# Laptimer.net
KiCad netlist of a schematic drawn in EAGLE
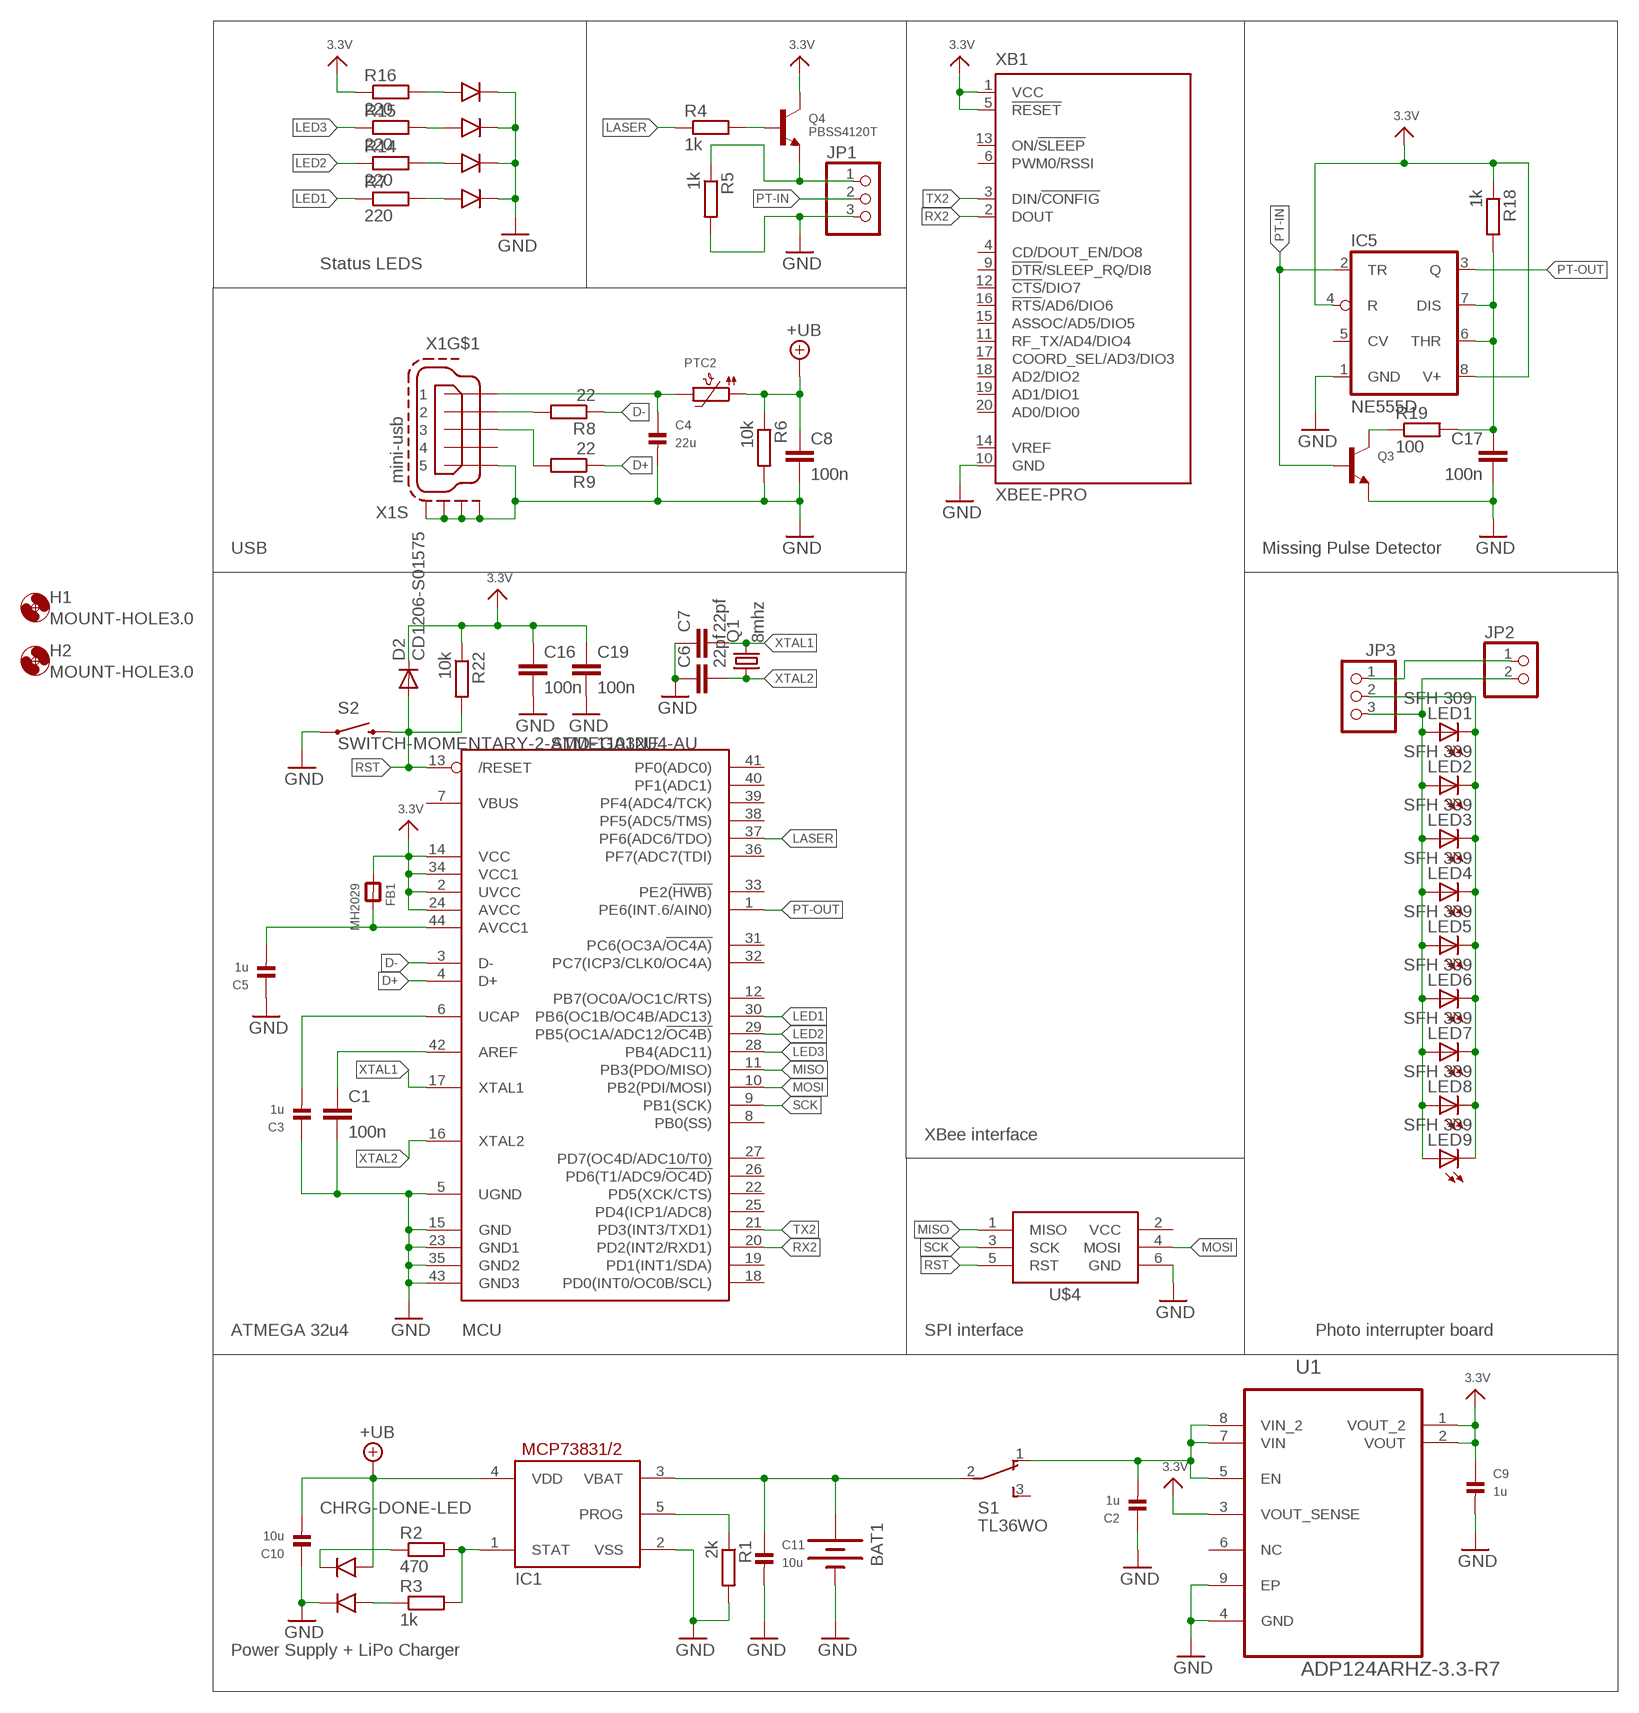
[diagram p0: schematic, sheet 1]

(export (version "E")
  (design (tool "Eeschema 10.0.6"))
  (components
    (comp (ref "BAT1")
      (value "BATTERY18650")
      (footprint "eagle-import:BATTERY_18650-HOLDER")
      (libsource (lib "eagle-import") (part "BATTERY18650"))
    )
    (comp (ref "C1")
      (value "100n")
      (footprint "eagle-import:C0603K")
      (libsource (lib "eagle-import") (part "C-EUC0603K"))
    )
    (comp (ref "C2")
      (value "1u")
      (footprint "eagle-import:_0805MP")
      (libsource (lib "eagle-import") (part "CAP_CERAMIC_0805MP"))
    )
    (comp (ref "C3")
      (value "1u")
      (footprint "eagle-import:_0805MP")
      (libsource (lib "eagle-import") (part "CAP_CERAMIC_0805MP"))
    )
    (comp (ref "C4")
      (value "22u")
      (footprint "eagle-import:_0805MP")
      (libsource (lib "eagle-import") (part "CAP_CERAMIC_0805MP"))
    )
    (comp (ref "C5")
      (value "1u")
      (footprint "eagle-import:_0805MP")
      (libsource (lib "eagle-import") (part "CAP_CERAMIC_0805MP"))
    )
    (comp (ref "C6")
      (value "22pf")
      (footprint "eagle-import:C0603K")
      (libsource (lib "eagle-import") (part "C-EUC0603K"))
    )
    (comp (ref "C7")
      (value "22pf")
      (footprint "eagle-import:C0603K")
      (libsource (lib "eagle-import") (part "C-EUC0603K"))
    )
    (comp (ref "C8")
      (value "100n")
      (footprint "eagle-import:C0603K")
      (libsource (lib "eagle-import") (part "C-EUC0603K"))
    )
    (comp (ref "C9")
      (value "1u")
      (footprint "eagle-import:_0805MP")
      (libsource (lib "eagle-import") (part "CAP_CERAMIC_0805MP"))
    )
    (comp (ref "C10")
      (value "10u")
      (footprint "eagle-import:_0805MP")
      (libsource (lib "eagle-import") (part "CAP_CERAMIC_0805MP"))
    )
    (comp (ref "C11")
      (value "10u")
      (footprint "eagle-import:_0805MP")
      (libsource (lib "eagle-import") (part "CAP_CERAMIC_0805MP"))
    )
    (comp (ref "C16")
      (value "100n")
      (footprint "eagle-import:C0603K")
      (libsource (lib "eagle-import") (part "C-EUC0603K"))
    )
    (comp (ref "C17")
      (value "100n")
      (footprint "eagle-import:C0603K")
      (libsource (lib "eagle-import") (part "C-EUC0603K"))
    )
    (comp (ref "C19")
      (value "100n")
      (footprint "eagle-import:C0603K")
      (libsource (lib "eagle-import") (part "C-EUC0603K"))
    )
    (comp (ref "D2")
      (value "CD1206-S01575")
      (footprint "eagle-import:MINIMELF")
      (libsource (lib "eagle-import") (part "DIODE-MINIMELF"))
    )
    (comp (ref "FB1")
      (value "MH2029")
      (footprint "eagle-import:_0805MP")
      (libsource (lib "eagle-import") (part "FERRITE_0805MP"))
    )
    (comp (ref "H1")
      (value "MOUNT-HOLE3.0")
      (footprint "eagle-import:3,0")
      (libsource (lib "eagle-import") (part "MOUNT-HOLE3.0"))
    )
    (comp (ref "H2")
      (value "MOUNT-HOLE3.0")
      (footprint "eagle-import:3,0")
      (libsource (lib "eagle-import") (part "MOUNT-HOLE3.0"))
    )
    (comp (ref "IC1")
      (value "MCP73831/OT")
      (footprint "eagle-import:SOT23-5L")
      (libsource (lib "eagle-import") (part "MCP73831/OT"))
    )
    (comp (ref "IC5")
      (value "NE555D")
      (footprint "eagle-import:SO08")
      (libsource (lib "eagle-import") (part "555DNE"))
    )
    (comp (ref "JP1")
      (value "PINHD-1X3")
      (footprint "eagle-import:1X03")
      (libsource (lib "eagle-import") (part "PINHD-1X3"))
    )
    (comp (ref "JP2")
      (value "HEADER-1X2ROUND")
      (footprint "eagle-import:1X02_ROUND")
      (libsource (lib "eagle-import") (part "HEADER-1X2ROUND"))
    )
    (comp (ref "JP3")
      (value "PINHD-1X3")
      (footprint "eagle-import:1X03")
      (libsource (lib "eagle-import") (part "PINHD-1X3"))
    )
    (comp (ref "LED1")
      (value "SFH 309")
      (footprint "eagle-import:LED3MM")
      (libsource (lib "eagle-import") (part "LED3MM"))
    )
    (comp (ref "LED2")
      (value "SFH 309")
      (footprint "eagle-import:LED3MM")
      (libsource (lib "eagle-import") (part "LED3MM"))
    )
    (comp (ref "LED3")
      (value "SFH 309")
      (footprint "eagle-import:LED3MM")
      (libsource (lib "eagle-import") (part "LED3MM"))
    )
    (comp (ref "LED4")
      (value "SFH 309")
      (footprint "eagle-import:LED3MM")
      (libsource (lib "eagle-import") (part "LED3MM"))
    )
    (comp (ref "LED5")
      (value "SFH 309")
      (footprint "eagle-import:LED3MM")
      (libsource (lib "eagle-import") (part "LED3MM"))
    )
    (comp (ref "LED6")
      (value "SFH 309")
      (footprint "eagle-import:LED3MM")
      (libsource (lib "eagle-import") (part "LED3MM"))
    )
    (comp (ref "LED7")
      (value "SFH 309")
      (footprint "eagle-import:LED3MM")
      (libsource (lib "eagle-import") (part "LED3MM"))
    )
    (comp (ref "LED8")
      (value "SFH 309")
      (footprint "eagle-import:LED3MM")
      (libsource (lib "eagle-import") (part "LED3MM"))
    )
    (comp (ref "LED9")
      (value "SFH 309")
      (footprint "eagle-import:LED3MM")
      (libsource (lib "eagle-import") (part "LED3MM"))
    )
    (comp (ref "MCU")
      (value "ATMEGA32U4-AU")
      (footprint "eagle-import:TQFP44")
      (libsource (lib "eagle-import") (part "ATMEGA32U4-AU"))
    )
    (comp (ref "PTC2")
      (value "PTC1206")
      (footprint "eagle-import:1206")
      (libsource (lib "eagle-import") (part "PTC1206"))
    )
    (comp (ref "Q1")
      (value "8mhz")
      (footprint "eagle-import:HC49_S")
      (libsource (lib "eagle-import") (part "CRYSTALHC49S"))
    )
    (comp (ref "Q3")
      (value "TRANSISTOR_NPNWIDE")
      (footprint "eagle-import:SOT23-WIDE")
      (libsource (lib "eagle-import") (part "TRANSISTOR_NPNWIDE"))
    )
    (comp (ref "Q4")
      (value "PBSS4120T")
      (footprint "eagle-import:SOT23-WIDE")
      (libsource (lib "eagle-import") (part "TRANSISTOR_NPNWIDE"))
    )
    (comp (ref "R1")
      (value "2k")
      (footprint "eagle-import:R0603")
      (libsource (lib "eagle-import") (part "R-EU_R0603"))
    )
    (comp (ref "R2")
      (value "470")
      (footprint "eagle-import:R0603")
      (libsource (lib "eagle-import") (part "R-EU_R0603"))
    )
    (comp (ref "R3")
      (value "1k")
      (footprint "eagle-import:R0603")
      (libsource (lib "eagle-import") (part "R-EU_R0603"))
    )
    (comp (ref "R4")
      (value "1k")
      (footprint "eagle-import:R0603")
      (libsource (lib "eagle-import") (part "R-EU_R0603"))
    )
    (comp (ref "R5")
      (value "1k")
      (footprint "eagle-import:R0603")
      (libsource (lib "eagle-import") (part "R-EU_R0603"))
    )
    (comp (ref "R6")
      (value "10k")
      (footprint "eagle-import:R0603")
      (libsource (lib "eagle-import") (part "R-EU_R0603"))
    )
    (comp (ref "R7")
      (value "220")
      (footprint "eagle-import:R0603")
      (libsource (lib "eagle-import") (part "R-EU_R0603"))
    )
    (comp (ref "R8")
      (value "22")
      (footprint "eagle-import:R0603")
      (libsource (lib "eagle-import") (part "R-EU_R0603"))
    )
    (comp (ref "R9")
      (value "22")
      (footprint "eagle-import:R0603")
      (libsource (lib "eagle-import") (part "R-EU_R0603"))
    )
    (comp (ref "R14")
      (value "220")
      (footprint "eagle-import:R0603")
      (libsource (lib "eagle-import") (part "R-EU_R0603"))
    )
    (comp (ref "R15")
      (value "220")
      (footprint "eagle-import:R0603")
      (libsource (lib "eagle-import") (part "R-EU_R0603"))
    )
    (comp (ref "R16")
      (value "220")
      (footprint "eagle-import:R0603")
      (libsource (lib "eagle-import") (part "R-EU_R0603"))
    )
    (comp (ref "R18")
      (value "1k")
      (footprint "eagle-import:R0603")
      (libsource (lib "eagle-import") (part "R-EU_R0603"))
    )
    (comp (ref "R19")
      (value "100")
      (footprint "eagle-import:R0603")
      (libsource (lib "eagle-import") (part "R-EU_R0603"))
    )
    (comp (ref "R22")
      (value "10k")
      (footprint "eagle-import:R0603")
      (libsource (lib "eagle-import") (part "R-EU_R0603"))
    )
    (comp (ref "S1")
      (value "TL36WO")
      (footprint "eagle-import:TL3XWO")
      (libsource (lib "eagle-import") (part "TL36WO"))
    )
    (comp (ref "S2")
      (value "SWITCH-MOMENTARY-2-SMD-1101NE")
      (footprint "eagle-import:TACTILE-SWITCH-1101NE")
      (libsource (lib "eagle-import") (part "SWITCH-MOMENTARY-2-SMD-1101NE"))
    )
    (comp (ref "U$1")
      (value "BI-LEVEL-LED-INDICATOR")
      (footprint "eagle-import:BI-LEVEL-LED-INDICATOR")
      (libsource (lib "eagle-import") (part "BI-LEVEL-LED-INDICATOR"))
    )
    (comp (ref "U$4")
      (value "AVRISP-BOX")
      (footprint "eagle-import:AVRISP-BOX")
      (libsource (lib "eagle-import") (part "AVRISP-BOX"))
    )
    (comp (ref "U$18")
      (value "BI-LEVEL-LED-INDICATOR")
      (footprint "eagle-import:BI-LEVEL-LED-INDICATOR")
      (libsource (lib "eagle-import") (part "BI-LEVEL-LED-INDICATOR"))
    )
    (comp (ref "U$19")
      (value "BI-LEVEL-LED-INDICATOR")
      (footprint "eagle-import:BI-LEVEL-LED-INDICATOR")
      (libsource (lib "eagle-import") (part "BI-LEVEL-LED-INDICATOR"))
    )
    (comp (ref "U1")
      (value "ADP124ARHZ-3.3-R7")
      (footprint "eagle-import:SOP65P490X110-9N")
      (libsource (lib "eagle-import") (part "ADP124ARHZ-3.3-R7"))
    )
    (comp (ref "X1")
      (value "mini-usb")
      (footprint "eagle-import:32005-301")
      (libsource (lib "eagle-import") (part "MINI-USB-SCHIELD-32005-301"))
    )
    (comp (ref "XB1")
      (value "XBEE-PRO")
      (footprint "eagle-import:XBEE-PRO")
      (libsource (lib "eagle-import") (part "XBEE-PRO"))
    )
  )
  (nets
    (net (code "1") (name "+UB") (class "Default")
      (node (ref "C10") (pin "2") (pinfunction "P$2_2") (pintype "passive"))
      (node (ref "C8") (pin "1") (pinfunction "1_1") (pintype "passive"))
      (node (ref "IC1") (pin "4") (pinfunction "VDD_4") (pintype "power_in"))
      (node (ref "PTC2") (pin "1") (pinfunction "1_1") (pintype "passive"))
      (node (ref "R6") (pin "1") (pinfunction "1_1") (pintype "passive"))
      (node (ref "U$1") (pin "ANODE1") (pinfunction "ANODE1_ANODE1") (pintype "bidirectional"))
    )
    (net (code "2") (name "/CHRG-DONE-LED") (class "Default")
      (node (ref "R3") (pin "1") (pinfunction "1_1") (pintype "passive"))
      (node (ref "U$1") (pin "ANODE2") (pinfunction "ANODE2_ANODE2") (pintype "bidirectional"))
    )
    (net (code "3") (name "/VCC") (class "Default")
      (node (ref "U$4") (pin "2") (pinfunction "VCC_2") (pintype "power_in"))
    )
    (net (code "4") (name "3.3V") (class "Default")
      (node (ref "C16") (pin "1") (pinfunction "1_1") (pintype "passive"))
      (node (ref "C19") (pin "1") (pinfunction "1_1") (pintype "passive"))
      (node (ref "C9") (pin "1") (pinfunction "P$1_1") (pintype "passive"))
      (node (ref "D2") (pin "C") (pinfunction "C_C") (pintype "passive"))
      (node (ref "FB1") (pin "1") (pinfunction "P$1_1") (pintype "passive"))
      (node (ref "IC5") (pin "4") (pinfunction "R_4") (pintype "input"))
      (node (ref "IC5") (pin "8") (pinfunction "V+_8") (pintype "power_in"))
      (node (ref "MCU") (pin "14") (pinfunction "VCC_14") (pintype "bidirectional"))
      (node (ref "MCU") (pin "2") (pinfunction "UVCC_2") (pintype "bidirectional"))
      (node (ref "MCU") (pin "24") (pinfunction "AVCC_24") (pintype "bidirectional"))
      (node (ref "MCU") (pin "34") (pinfunction "VCC1_34") (pintype "bidirectional"))
      (node (ref "Q4") (pin "3") (pinfunction "C_3") (pintype "passive"))
      (node (ref "R16") (pin "1") (pinfunction "1_1") (pintype "passive"))
      (node (ref "R18") (pin "1") (pinfunction "1_1") (pintype "passive"))
      (node (ref "R22") (pin "1") (pinfunction "1_1") (pintype "passive"))
      (node (ref "U1") (pin "1") (pinfunction "VOUT_2_1") (pintype "output"))
      (node (ref "U1") (pin "2") (pinfunction "VOUT_2") (pintype "output"))
      (node (ref "U1") (pin "3") (pinfunction "VOUT_SENSE_3") (pintype "input"))
      (node (ref "XB1") (pin "1") (pinfunction "VCC_1") (pintype "power_in"))
      (node (ref "XB1") (pin "5") (pinfunction "~{RESET}_5") (pintype "input"))
    )
    (net (code "5") (name "D+") (class "Default")
      (node (ref "MCU") (pin "4") (pinfunction "D+_4") (pintype "bidirectional"))
      (node (ref "R9") (pin "1") (pinfunction "1_1") (pintype "passive"))
    )
    (net (code "6") (name "D-") (class "Default")
      (node (ref "MCU") (pin "3") (pinfunction "D-_3") (pintype "bidirectional"))
      (node (ref "R8") (pin "1") (pinfunction "1_1") (pintype "passive"))
    )
    (net (code "7") (name "GND") (class "Default")
      (node (ref "BAT1") (pin "GND@1") (pinfunction "-_GND@1") (pintype "power_in"))
      (node (ref "C1") (pin "2") (pinfunction "2_2") (pintype "passive"))
      (node (ref "C10") (pin "1") (pinfunction "P$1_1") (pintype "passive"))
      (node (ref "C11") (pin "2") (pinfunction "P$2_2") (pintype "passive"))
      (node (ref "C16") (pin "2") (pinfunction "2_2") (pintype "passive"))
      (node (ref "C17") (pin "2") (pinfunction "2_2") (pintype "passive"))
      (node (ref "C19") (pin "2") (pinfunction "2_2") (pintype "passive"))
      (node (ref "C2") (pin "1") (pinfunction "P$1_1") (pintype "passive"))
      (node (ref "C3") (pin "1") (pinfunction "P$1_1") (pintype "passive"))
      (node (ref "C4") (pin "2") (pinfunction "P$2_2") (pintype "passive"))
      (node (ref "C5") (pin "1") (pinfunction "P$1_1") (pintype "passive"))
      (node (ref "C6") (pin "1") (pinfunction "1_1") (pintype "passive"))
      (node (ref "C7") (pin "1") (pinfunction "1_1") (pintype "passive"))
      (node (ref "C8") (pin "2") (pinfunction "2_2") (pintype "passive"))
      (node (ref "C9") (pin "2") (pinfunction "P$2_2") (pintype "passive"))
      (node (ref "IC1") (pin "2") (pinfunction "VSS_2") (pintype "power_in"))
      (node (ref "IC5") (pin "1") (pinfunction "GND_1") (pintype "power_in"))
      (node (ref "JP1") (pin "3") (pinfunction "3_3") (pintype "passive"))
      (node (ref "MCU") (pin "15") (pinfunction "GND_15") (pintype "bidirectional"))
      (node (ref "MCU") (pin "23") (pinfunction "GND1_23") (pintype "bidirectional"))
      (node (ref "MCU") (pin "35") (pinfunction "GND2_35") (pintype "bidirectional"))
      (node (ref "MCU") (pin "43") (pinfunction "GND3_43") (pintype "bidirectional"))
      (node (ref "MCU") (pin "5") (pinfunction "UGND_5") (pintype "bidirectional"))
      (node (ref "Q3") (pin "2") (pinfunction "E_2") (pintype "passive"))
      (node (ref "R1") (pin "2") (pinfunction "2_2") (pintype "passive"))
      (node (ref "R5") (pin "2") (pinfunction "2_2") (pintype "passive"))
      (node (ref "R6") (pin "2") (pinfunction "2_2") (pintype "passive"))
      (node (ref "S2") (pin "P$1") (pinfunction "1_P$1") (pintype "passive"))
      (node (ref "U$1") (pin "CATHODE2") (pinfunction "CATHODE2_CATHODE2") (pintype "bidirectional"))
      (node (ref "U$18") (pin "CATHODE1") (pinfunction "CATHODE1_CATHODE1") (pintype "bidirectional"))
      (node (ref "U$18") (pin "CATHODE2") (pinfunction "CATHODE2_CATHODE2") (pintype "bidirectional"))
      (node (ref "U$19") (pin "CATHODE1") (pinfunction "CATHODE1_CATHODE1") (pintype "bidirectional"))
      (node (ref "U$19") (pin "CATHODE2") (pinfunction "CATHODE2_CATHODE2") (pintype "bidirectional"))
      (node (ref "U$4") (pin "6") (pinfunction "GND_6") (pintype "power_in"))
      (node (ref "U1") (pin "4") (pinfunction "GND_4") (pintype "passive"))
      (node (ref "U1") (pin "9") (pinfunction "EP_9") (pintype "passive"))
      (node (ref "X1") (pin "5") (pinfunction "5_5") (pintype "passive"))
      (node (ref "X1") (pin "M1") (pinfunction "S1_M1") (pintype "passive"))
      (node (ref "X1") (pin "M2") (pinfunction "S2_M2") (pintype "passive"))
      (node (ref "X1") (pin "M3") (pinfunction "S3_M3") (pintype "passive"))
      (node (ref "X1") (pin "M4") (pinfunction "S4_M4") (pintype "passive"))
      (node (ref "XB1") (pin "10") (pinfunction "GND_10") (pintype "power_in"))
    )
    (net (code "8") (name "LASER") (class "Default")
      (node (ref "MCU") (pin "37") (pinfunction "PF6(ADC6/TDO)_37") (pintype "bidirectional"))
      (node (ref "R4") (pin "1") (pinfunction "1_1") (pintype "passive"))
    )
    (net (code "9") (name "LED1") (class "Default")
      (node (ref "MCU") (pin "30") (pinfunction "PB6(OC1B/OC4B/ADC13)_30") (pintype "bidirectional"))
      (node (ref "R7") (pin "1") (pinfunction "1_1") (pintype "passive"))
    )
    (net (code "10") (name "LED2") (class "Default")
      (node (ref "MCU") (pin "29") (pinfunction "PB5(OC1A/ADC12/~{OC4B})_29") (pintype "bidirectional"))
      (node (ref "R14") (pin "1") (pinfunction "1_1") (pintype "passive"))
    )
    (net (code "11") (name "LED3") (class "Default")
      (node (ref "MCU") (pin "28") (pinfunction "PB4(ADC11)_28") (pintype "bidirectional"))
      (node (ref "R15") (pin "1") (pinfunction "1_1") (pintype "passive"))
    )
    (net (code "12") (name "MISO") (class "Default")
      (node (ref "MCU") (pin "11") (pinfunction "PB3(PDO/MISO)_11") (pintype "bidirectional"))
      (node (ref "U$4") (pin "1") (pinfunction "MISO_1") (pintype "input"))
    )
    (net (code "13") (name "MOSI") (class "Default")
      (node (ref "MCU") (pin "10") (pinfunction "PB2(PDI/MOSI)_10") (pintype "bidirectional"))
      (node (ref "U$4") (pin "4") (pinfunction "MOSI_4") (pintype "output"))
    )
    (net (code "14") (name "Net-(BAT1-+)") (class "Default")
      (node (ref "BAT1") (pin "PWR@1") (pinfunction "+_PWR@1") (pintype "power_in"))
      (node (ref "C11") (pin "1") (pinfunction "P$1_1") (pintype "passive"))
      (node (ref "IC1") (pin "3") (pinfunction "VBAT_3") (pintype "bidirectional"))
      (node (ref "S1") (pin "2") (pinfunction "P_2") (pintype "passive"))
    )
    (net (code "15") (name "Net-(C2-P$2)") (class "Default")
      (node (ref "C2") (pin "2") (pinfunction "P$2_2") (pintype "passive"))
      (node (ref "S1") (pin "1") (pinfunction "O_1") (pintype "passive"))
      (node (ref "U1") (pin "5") (pinfunction "EN_5") (pintype "input"))
      (node (ref "U1") (pin "7") (pinfunction "VIN_7") (pintype "power_in"))
      (node (ref "U1") (pin "8") (pinfunction "VIN_2_8") (pintype "power_in"))
    )
    (net (code "16") (name "Net-(C3-P$2)") (class "Default")
      (node (ref "C3") (pin "2") (pinfunction "P$2_2") (pintype "passive"))
      (node (ref "MCU") (pin "6") (pinfunction "UCAP_6") (pintype "bidirectional"))
    )
    (net (code "17") (name "Net-(C4-P$1)") (class "Default")
      (node (ref "C4") (pin "1") (pinfunction "P$1_1") (pintype "passive"))
      (node (ref "PTC2") (pin "2") (pinfunction "2_2") (pintype "passive"))
      (node (ref "X1") (pin "1") (pinfunction "1_1") (pintype "passive"))
    )
    (net (code "18") (name "Net-(C5-P$2)") (class "Default")
      (node (ref "C5") (pin "2") (pinfunction "P$2_2") (pintype "passive"))
      (node (ref "FB1") (pin "2") (pinfunction "P$2_2") (pintype "passive"))
      (node (ref "MCU") (pin "44") (pinfunction "AVCC1_44") (pintype "bidirectional"))
    )
    (net (code "19") (name "Net-(IC1-PROG)") (class "Default")
      (node (ref "IC1") (pin "5") (pinfunction "PROG_5") (pintype "input"))
      (node (ref "R1") (pin "1") (pinfunction "1_1") (pintype "passive"))
    )
    (net (code "20") (name "Net-(IC1-STAT)") (class "Default")
      (node (ref "IC1") (pin "1") (pinfunction "STAT_1") (pintype "output"))
      (node (ref "R2") (pin "2") (pinfunction "2_2") (pintype "passive"))
      (node (ref "R3") (pin "2") (pinfunction "2_2") (pintype "passive"))
    )
    (net (code "21") (name "Net-(IC5-DIS)") (class "Default")
      (node (ref "C17") (pin "1") (pinfunction "1_1") (pintype "passive"))
      (node (ref "IC5") (pin "6") (pinfunction "THR_6") (pintype "input"))
      (node (ref "IC5") (pin "7") (pinfunction "DIS_7") (pintype "input"))
      (node (ref "R18") (pin "2") (pinfunction "2_2") (pintype "passive"))
      (node (ref "R19") (pin "2") (pinfunction "2_2") (pintype "passive"))
    )
    (net (code "22") (name "Net-(JP2-Pad1)") (class "Default")
      (node (ref "JP2") (pin "1") (pinfunction "1_1") (pintype "passive"))
      (node (ref "JP3") (pin "1") (pinfunction "1_1") (pintype "passive"))
    )
    (net (code "23") (name "Net-(JP2-Pad2)") (class "Default")
      (node (ref "JP2") (pin "2") (pinfunction "2_2") (pintype "passive"))
      (node (ref "JP3") (pin "3") (pinfunction "3_3") (pintype "passive"))
      (node (ref "LED1") (pin "A") (pinfunction "A_A") (pintype "passive"))
      (node (ref "LED2") (pin "A") (pinfunction "A_A") (pintype "passive"))
      (node (ref "LED3") (pin "A") (pinfunction "A_A") (pintype "passive"))
      (node (ref "LED4") (pin "A") (pinfunction "A_A") (pintype "passive"))
      (node (ref "LED5") (pin "A") (pinfunction "A_A") (pintype "passive"))
      (node (ref "LED6") (pin "A") (pinfunction "A_A") (pintype "passive"))
      (node (ref "LED7") (pin "A") (pinfunction "A_A") (pintype "passive"))
      (node (ref "LED8") (pin "A") (pinfunction "A_A") (pintype "passive"))
      (node (ref "LED9") (pin "A") (pinfunction "A_A") (pintype "passive"))
    )
    (net (code "24") (name "Net-(LED1-C)") (class "Default")
      (node (ref "JP3") (pin "2") (pinfunction "2_2") (pintype "passive"))
      (node (ref "LED1") (pin "K") (pinfunction "C_K") (pintype "passive"))
      (node (ref "LED2") (pin "K") (pinfunction "C_K") (pintype "passive"))
      (node (ref "LED3") (pin "K") (pinfunction "C_K") (pintype "passive"))
      (node (ref "LED4") (pin "K") (pinfunction "C_K") (pintype "passive"))
      (node (ref "LED5") (pin "K") (pinfunction "C_K") (pintype "passive"))
      (node (ref "LED6") (pin "K") (pinfunction "C_K") (pintype "passive"))
      (node (ref "LED7") (pin "K") (pinfunction "C_K") (pintype "passive"))
      (node (ref "LED8") (pin "K") (pinfunction "C_K") (pintype "passive"))
      (node (ref "LED9") (pin "K") (pinfunction "C_K") (pintype "passive"))
    )
    (net (code "25") (name "Net-(MCU-AREF)") (class "Default")
      (node (ref "C1") (pin "1") (pinfunction "1_1") (pintype "passive"))
      (node (ref "MCU") (pin "42") (pinfunction "AREF_42") (pintype "bidirectional"))
    )
    (net (code "26") (name "Net-(Q3-C)") (class "Default")
      (node (ref "Q3") (pin "3") (pinfunction "C_3") (pintype "passive"))
      (node (ref "R19") (pin "1") (pinfunction "1_1") (pintype "passive"))
    )
    (net (code "27") (name "Net-(Q4-B)") (class "Default")
      (node (ref "Q4") (pin "1") (pinfunction "B_1") (pintype "passive"))
      (node (ref "R4") (pin "2") (pinfunction "2_2") (pintype "passive"))
    )
    (net (code "28") (name "Net-(Q4-E)") (class "Default")
      (node (ref "JP1") (pin "1") (pinfunction "1_1") (pintype "passive"))
      (node (ref "Q4") (pin "2") (pinfunction "E_2") (pintype "passive"))
      (node (ref "R5") (pin "1") (pinfunction "1_1") (pintype "passive"))
    )
    (net (code "29") (name "Net-(R2-Pad1)") (class "Default")
      (node (ref "R2") (pin "1") (pinfunction "1_1") (pintype "passive"))
      (node (ref "U$1") (pin "CATHODE1") (pinfunction "CATHODE1_CATHODE1") (pintype "bidirectional"))
    )
    (net (code "30") (name "Net-(R7-Pad2)") (class "Default")
      (node (ref "R7") (pin "2") (pinfunction "2_2") (pintype "passive"))
      (node (ref "U$18") (pin "ANODE1") (pinfunction "ANODE1_ANODE1") (pintype "bidirectional"))
    )
    (net (code "31") (name "Net-(R8-Pad2)") (class "Default")
      (node (ref "R8") (pin "2") (pinfunction "2_2") (pintype "passive"))
      (node (ref "X1") (pin "2") (pinfunction "2_2") (pintype "passive"))
    )
    (net (code "32") (name "Net-(R9-Pad2)") (class "Default")
      (node (ref "R9") (pin "2") (pinfunction "2_2") (pintype "passive"))
      (node (ref "X1") (pin "3") (pinfunction "3_3") (pintype "passive"))
    )
    (net (code "33") (name "Net-(R14-Pad2)") (class "Default")
      (node (ref "R14") (pin "2") (pinfunction "2_2") (pintype "passive"))
      (node (ref "U$18") (pin "ANODE2") (pinfunction "ANODE2_ANODE2") (pintype "bidirectional"))
    )
    (net (code "34") (name "Net-(R15-Pad2)") (class "Default")
      (node (ref "R15") (pin "2") (pinfunction "2_2") (pintype "passive"))
      (node (ref "U$19") (pin "ANODE1") (pinfunction "ANODE1_ANODE1") (pintype "bidirectional"))
    )
    (net (code "35") (name "Net-(R16-Pad2)") (class "Default")
      (node (ref "R16") (pin "2") (pinfunction "2_2") (pintype "passive"))
      (node (ref "U$19") (pin "ANODE2") (pinfunction "ANODE2_ANODE2") (pintype "bidirectional"))
    )
    (net (code "36") (name "PT-IN") (class "Default")
      (node (ref "IC5") (pin "2") (pinfunction "TR_2") (pintype "input"))
      (node (ref "JP1") (pin "2") (pinfunction "2_2") (pintype "passive"))
      (node (ref "Q3") (pin "1") (pinfunction "B_1") (pintype "passive"))
    )
    (net (code "37") (name "PT-OUT") (class "Default")
      (node (ref "IC5") (pin "3") (pinfunction "Q_3") (pintype "output"))
      (node (ref "MCU") (pin "1") (pinfunction "PE6(INT.6/AIN0)_1") (pintype "bidirectional"))
    )
    (net (code "38") (name "RST") (class "Default")
      (node (ref "D2") (pin "A") (pinfunction "A_A") (pintype "passive"))
      (node (ref "MCU") (pin "13") (pinfunction "/RESET_13") (pintype "bidirectional"))
      (node (ref "R22") (pin "2") (pinfunction "2_2") (pintype "passive"))
      (node (ref "S2") (pin "P$2") (pinfunction "2_P$2") (pintype "passive"))
      (node (ref "U$4") (pin "5") (pinfunction "RST_5") (pintype "output"))
    )
    (net (code "39") (name "RX2") (class "Default")
      (node (ref "MCU") (pin "20") (pinfunction "PD2(INT2/RXD1)_20") (pintype "bidirectional"))
      (node (ref "XB1") (pin "2") (pinfunction "DOUT_2") (pintype "output"))
    )
    (net (code "40") (name "SCK") (class "Default")
      (node (ref "MCU") (pin "9") (pinfunction "PB1(SCK)_9") (pintype "bidirectional"))
      (node (ref "U$4") (pin "3") (pinfunction "SCK_3") (pintype "output"))
    )
    (net (code "41") (name "TX2") (class "Default")
      (node (ref "MCU") (pin "21") (pinfunction "PD3(INT3/TXD1)_21") (pintype "bidirectional"))
      (node (ref "XB1") (pin "3") (pinfunction "DIN/~{CONFIG}_3") (pintype "input"))
    )
    (net (code "42") (name "XTAL1") (class "Default")
      (node (ref "C7") (pin "2") (pinfunction "2_2") (pintype "passive"))
      (node (ref "MCU") (pin "17") (pinfunction "XTAL1_17") (pintype "bidirectional"))
      (node (ref "Q1") (pin "2") (pinfunction "2_2") (pintype "passive"))
    )
    (net (code "43") (name "XTAL2") (class "Default")
      (node (ref "C6") (pin "2") (pinfunction "2_2") (pintype "passive"))
      (node (ref "MCU") (pin "16") (pinfunction "XTAL2_16") (pintype "bidirectional"))
      (node (ref "Q1") (pin "1") (pinfunction "1_1") (pintype "passive"))
    )
    (net (code "44") (name "unconnected-(IC5-CV-Pad5)") (class "Default")
      (node (ref "IC5") (pin "5") (pinfunction "CV_5") (pintype "input"))
    )
    (net (code "45") (name "unconnected-(MCU-PB0(SS)-Pad8)") (class "Default")
      (node (ref "MCU") (pin "8") (pinfunction "PB0(SS)_8") (pintype "bidirectional"))
    )
    (net (code "46") (name "unconnected-(MCU-PB7(OC0A{slash}OC1C{slash}RTS)-Pad12)") (class "Default")
      (node (ref "MCU") (pin "12") (pinfunction "PB7(OC0A/OC1C/RTS)_12") (pintype "bidirectional"))
    )
    (net (code "47") (name "unconnected-(MCU-PC6(OC3A{slash}~{OC4A})-Pad31)") (class "Default")
      (node (ref "MCU") (pin "31") (pinfunction "PC6(OC3A/~{OC4A})_31") (pintype "bidirectional"))
    )
    (net (code "48") (name "unconnected-(MCU-PC7(ICP3{slash}CLK0{slash}OC4A)-Pad32)") (class "Default")
      (node (ref "MCU") (pin "32") (pinfunction "PC7(ICP3/CLK0/OC4A)_32") (pintype "bidirectional"))
    )
    (net (code "49") (name "unconnected-(MCU-PD0(INT0{slash}OC0B{slash}SCL)-Pad18)") (class "Default")
      (node (ref "MCU") (pin "18") (pinfunction "PD0(INT0/OC0B/SCL)_18") (pintype "bidirectional"))
    )
    (net (code "50") (name "unconnected-(MCU-PD1(INT1{slash}SDA)-Pad19)") (class "Default")
      (node (ref "MCU") (pin "19") (pinfunction "PD1(INT1/SDA)_19") (pintype "bidirectional"))
    )
    (net (code "51") (name "unconnected-(MCU-PD4(ICP1{slash}ADC8)-Pad25)") (class "Default")
      (node (ref "MCU") (pin "25") (pinfunction "PD4(ICP1/ADC8)_25") (pintype "bidirectional"))
    )
    (net (code "52") (name "unconnected-(MCU-PD5(XCK{slash}CTS)-Pad22)") (class "Default")
      (node (ref "MCU") (pin "22") (pinfunction "PD5(XCK/CTS)_22") (pintype "bidirectional"))
    )
    (net (code "53") (name "unconnected-(MCU-PD6(T1{slash}ADC9{slash}~{OC4D})-Pad26)") (class "Default")
      (node (ref "MCU") (pin "26") (pinfunction "PD6(T1/ADC9/~{OC4D})_26") (pintype "bidirectional"))
    )
    (net (code "54") (name "unconnected-(MCU-PD7(OC4D{slash}ADC10{slash}T0)-Pad27)") (class "Default")
      (node (ref "MCU") (pin "27") (pinfunction "PD7(OC4D/ADC10/T0)_27") (pintype "bidirectional"))
    )
    (net (code "55") (name "unconnected-(MCU-PE2(~{HWB})-Pad33)") (class "Default")
      (node (ref "MCU") (pin "33") (pinfunction "PE2(~{HWB})_33") (pintype "bidirectional"))
    )
    (net (code "56") (name "unconnected-(MCU-PF0(ADC0)-Pad41)") (class "Default")
      (node (ref "MCU") (pin "41") (pinfunction "PF0(ADC0)_41") (pintype "bidirectional"))
    )
    (net (code "57") (name "unconnected-(MCU-PF1(ADC1)-Pad40)") (class "Default")
      (node (ref "MCU") (pin "40") (pinfunction "PF1(ADC1)_40") (pintype "bidirectional"))
    )
    (net (code "58") (name "unconnected-(MCU-PF4(ADC4{slash}TCK)-Pad39)") (class "Default")
      (node (ref "MCU") (pin "39") (pinfunction "PF4(ADC4/TCK)_39") (pintype "bidirectional"))
    )
    (net (code "59") (name "unconnected-(MCU-PF5(ADC5{slash}TMS)-Pad38)") (class "Default")
      (node (ref "MCU") (pin "38") (pinfunction "PF5(ADC5/TMS)_38") (pintype "bidirectional"))
    )
    (net (code "60") (name "unconnected-(MCU-PF7(ADC7(TDI)-Pad36)") (class "Default")
      (node (ref "MCU") (pin "36") (pinfunction "PF7(ADC7(TDI)_36") (pintype "bidirectional"))
    )
    (net (code "61") (name "unconnected-(MCU-VBUS-Pad7)") (class "Default")
      (node (ref "MCU") (pin "7") (pinfunction "VBUS_7") (pintype "bidirectional"))
    )
    (net (code "62") (name "unconnected-(S1-S-Pad3)") (class "Default")
      (node (ref "S1") (pin "3") (pinfunction "S_3") (pintype "passive"))
    )
    (net (code "63") (name "unconnected-(U1-NC-Pad6)") (class "Default")
      (node (ref "U1") (pin "6") (pinfunction "NC_6") (pintype "no_connect"))
    )
    (net (code "64") (name "unconnected-(X1-Pad4)") (class "Default")
      (node (ref "X1") (pin "4") (pinfunction "4_4") (pintype "passive"))
    )
    (net (code "65") (name "unconnected-(XB1-AD0{slash}DIO0-Pad20)") (class "Default")
      (node (ref "XB1") (pin "20") (pinfunction "AD0/DIO0_20") (pintype "bidirectional"))
    )
    (net (code "66") (name "unconnected-(XB1-AD1{slash}DIO1-Pad19)") (class "Default")
      (node (ref "XB1") (pin "19") (pinfunction "AD1/DIO1_19") (pintype "bidirectional"))
    )
    (net (code "67") (name "unconnected-(XB1-AD2{slash}DIO2-Pad18)") (class "Default")
      (node (ref "XB1") (pin "18") (pinfunction "AD2/DIO2_18") (pintype "bidirectional"))
    )
    (net (code "68") (name "unconnected-(XB1-ASSOC{slash}AD5{slash}DIO5-Pad15)") (class "Default")
      (node (ref "XB1") (pin "15") (pinfunction "ASSOC/AD5/DIO5_15") (pintype "bidirectional"))
    )
    (net (code "69") (name "unconnected-(XB1-CD{slash}DOUT_EN{slash}DO8-Pad4)") (class "Default")
      (node (ref "XB1") (pin "4") (pinfunction "CD/DOUT_EN/DO8_4") (pintype "output"))
    )
    (net (code "70") (name "unconnected-(XB1-COORD_SEL{slash}AD3{slash}DIO3-Pad17)") (class "Default")
      (node (ref "XB1") (pin "17") (pinfunction "COORD_SEL/AD3/DIO3_17") (pintype "bidirectional"))
    )
    (net (code "71") (name "unconnected-(XB1-ON{slash}~{SLEEP}-Pad13)") (class "Default")
      (node (ref "XB1") (pin "13") (pinfunction "ON/~{SLEEP}_13") (pintype "output"))
    )
    (net (code "72") (name "unconnected-(XB1-PWM0{slash}RSSI-Pad6)") (class "Default")
      (node (ref "XB1") (pin "6") (pinfunction "PWM0/RSSI_6") (pintype "output"))
    )
    (net (code "73") (name "unconnected-(XB1-RF_TX{slash}AD4{slash}DIO4-Pad11)") (class "Default")
      (node (ref "XB1") (pin "11") (pinfunction "RF_TX/AD4/DIO4_11") (pintype "bidirectional"))
    )
    (net (code "74") (name "unconnected-(XB1-VREF-Pad14)") (class "Default")
      (node (ref "XB1") (pin "14") (pinfunction "VREF_14") (pintype "input"))
    )
    (net (code "75") (name "unconnected-(XB1-~{CTS}{slash}DIO7-Pad12)") (class "Default")
      (node (ref "XB1") (pin "12") (pinfunction "~{CTS}/DIO7_12") (pintype "bidirectional"))
    )
    (net (code "76") (name "unconnected-(XB1-~{DTR}{slash}SLEEP_RQ{slash}DI8-Pad9)") (class "Default")
      (node (ref "XB1") (pin "9") (pinfunction "~{DTR}/SLEEP_RQ/DI8_9") (pintype "bidirectional"))
    )
    (net (code "77") (name "unconnected-(XB1-~{RTS}{slash}AD6{slash}DIO6-Pad16)") (class "Default")
      (node (ref "XB1") (pin "16") (pinfunction "~{RTS}/AD6/DIO6_16") (pintype "bidirectional"))
    )
  )
)
